# AS5040.net
KiCad netlist of a schematic drawn in EAGLE
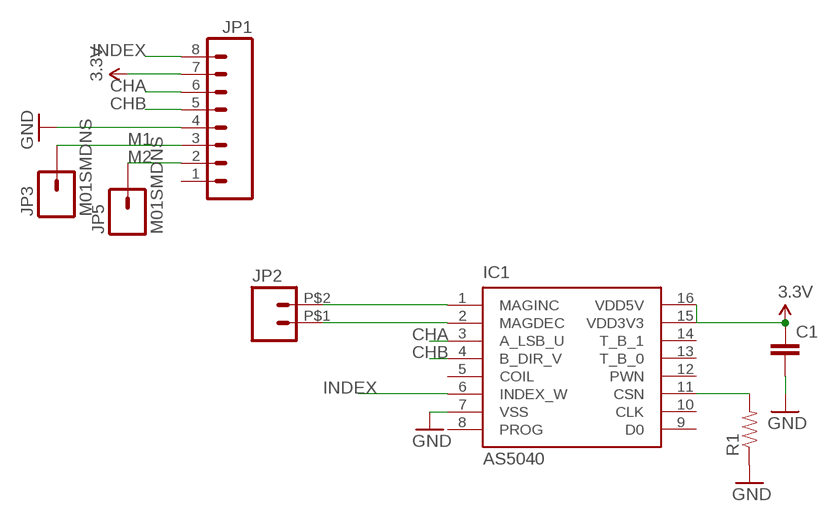
[diagram p0: schematic, sheet 1]

(export (version "E")
  (design (tool "Eeschema 10.0.6"))
  (components
    (comp (ref "C1")
      (value "CAP0603-CAP")
      (footprint "eagle-import:0603-CAP")
      (libsource (lib "eagle-import") (part "CAP0603-CAP"))
    )
    (comp (ref "IC1")
      (value "AS5040")
      (footprint "eagle-import:SSOP16")
      (fields (field (name "MPN") "AS5040ASSU"))
      (libsource (lib "eagle-import") (part "AS5040"))
    )
    (comp (ref "JP1")
      (value "M08")
      (footprint "eagle-import:BM08B")
      (libsource (lib "eagle-import") (part "M08"))
    )
    (comp (ref "JP2")
      (value "M02")
      (footprint "eagle-import:1X2SMD")
      (libsource (lib "eagle-import") (part "M02"))
    )
    (comp (ref "JP3")
      (value "M01SMDNS")
      (footprint "eagle-import:1X01NS")
      (libsource (lib "eagle-import") (part "M01SMDNS"))
    )
    (comp (ref "JP5")
      (value "M01SMDNS")
      (footprint "eagle-import:1X01NS")
      (libsource (lib "eagle-import") (part "M01SMDNS"))
    )
    (comp (ref "R1")
      (value "RESISTOR0603-RES")
      (footprint "eagle-import:0603-RES")
      (libsource (lib "eagle-import") (part "RESISTOR0603-RES"))
    )
  )
  (nets
    (net (code "1") (name "/CHA") (class "Default")
      (node (ref "IC1") (pin "3") (pinfunction "A_LSB_U_3") (pintype "output"))
      (node (ref "JP1") (pin "6") (pinfunction "6_6") (pintype "passive"))
    )
    (net (code "2") (name "/CHB") (class "Default")
      (node (ref "IC1") (pin "4") (pinfunction "B_DIR_V_4") (pintype "output"))
      (node (ref "JP1") (pin "5") (pinfunction "5_5") (pintype "passive"))
    )
    (net (code "3") (name "/INDEX") (class "Default")
      (node (ref "IC1") (pin "6") (pinfunction "INDEX_W_6") (pintype "output"))
      (node (ref "JP1") (pin "8") (pinfunction "8_8") (pintype "passive"))
    )
    (net (code "4") (name "/M1") (class "Default")
      (node (ref "JP1") (pin "3") (pinfunction "3_3") (pintype "passive"))
      (node (ref "JP3") (pin "1") (pinfunction "1_1") (pintype "passive"))
    )
    (net (code "5") (name "/M2") (class "Default")
      (node (ref "JP1") (pin "2") (pinfunction "2_2") (pintype "passive"))
      (node (ref "JP5") (pin "1") (pinfunction "1_1") (pintype "passive"))
    )
    (net (code "6") (name "3.3V") (class "Default")
      (node (ref "C1") (pin "1") (pinfunction "1_1") (pintype "passive"))
      (node (ref "IC1") (pin "15") (pinfunction "VDD3V3_15") (pintype "passive"))
      (node (ref "IC1") (pin "16") (pinfunction "VDD5V_16") (pintype "passive"))
      (node (ref "JP1") (pin "7") (pinfunction "7_7") (pintype "passive"))
    )
    (net (code "7") (name "GND") (class "Default")
      (node (ref "C1") (pin "2") (pinfunction "2_2") (pintype "passive"))
      (node (ref "IC1") (pin "7") (pinfunction "VSS_7") (pintype "passive"))
      (node (ref "JP1") (pin "4") (pinfunction "4_4") (pintype "passive"))
      (node (ref "R1") (pin "1") (pinfunction "1_1") (pintype "passive"))
    )
    (net (code "8") (name "Net-(IC1-CSN)") (class "Default")
      (node (ref "IC1") (pin "11") (pinfunction "CSN_11") (pintype "input"))
      (node (ref "R1") (pin "2") (pinfunction "2_2") (pintype "passive"))
    )
    (net (code "9") (name "Net-(IC1-MAGDEC)") (class "Default")
      (node (ref "IC1") (pin "2") (pinfunction "MAGDEC_2") (pintype "tri_state"))
      (node (ref "JP2") (pin "P$1") (pinfunction "1_P$1") (pintype "passive"))
    )
    (net (code "10") (name "Net-(IC1-MAGINC)") (class "Default")
      (node (ref "IC1") (pin "1") (pinfunction "MAGINC_1") (pintype "tri_state"))
      (node (ref "JP2") (pin "P$2") (pinfunction "2_P$2") (pintype "passive"))
    )
    (net (code "11") (name "unconnected-(IC1-CLK-Pad10)") (class "Default")
      (node (ref "IC1") (pin "10") (pinfunction "CLK_10") (pintype "input"))
    )
    (net (code "12") (name "unconnected-(IC1-COIL-Pad5)") (class "Default")
      (node (ref "IC1") (pin "5") (pinfunction "COIL_5") (pintype "no_connect"))
    )
    (net (code "13") (name "unconnected-(IC1-D0-Pad9)") (class "Default")
      (node (ref "IC1") (pin "9") (pinfunction "D0_9") (pintype "tri_state"))
    )
    (net (code "14") (name "unconnected-(IC1-PROG-Pad8)") (class "Default")
      (node (ref "IC1") (pin "8") (pinfunction "PROG_8") (pintype "input"))
    )
    (net (code "15") (name "unconnected-(IC1-PWN-Pad12)") (class "Default")
      (node (ref "IC1") (pin "12") (pinfunction "PWN_12") (pintype "passive"))
    )
    (net (code "16") (name "unconnected-(IC1-T_B_0-Pad13)") (class "Default")
      (node (ref "IC1") (pin "13") (pinfunction "T_B_0_13") (pintype "no_connect"))
    )
    (net (code "17") (name "unconnected-(IC1-T_B_1-Pad14)") (class "Default")
      (node (ref "IC1") (pin "14") (pinfunction "T_B_1_14") (pintype "no_connect"))
    )
    (net (code "18") (name "unconnected-(JP1-Pad1)") (class "Default")
      (node (ref "JP1") (pin "1") (pinfunction "1_1") (pintype "passive"))
    )
  )
)
